# 05_-_POWER_REGULATION.net
KiCad netlist of a schematic drawn in Altium Designer
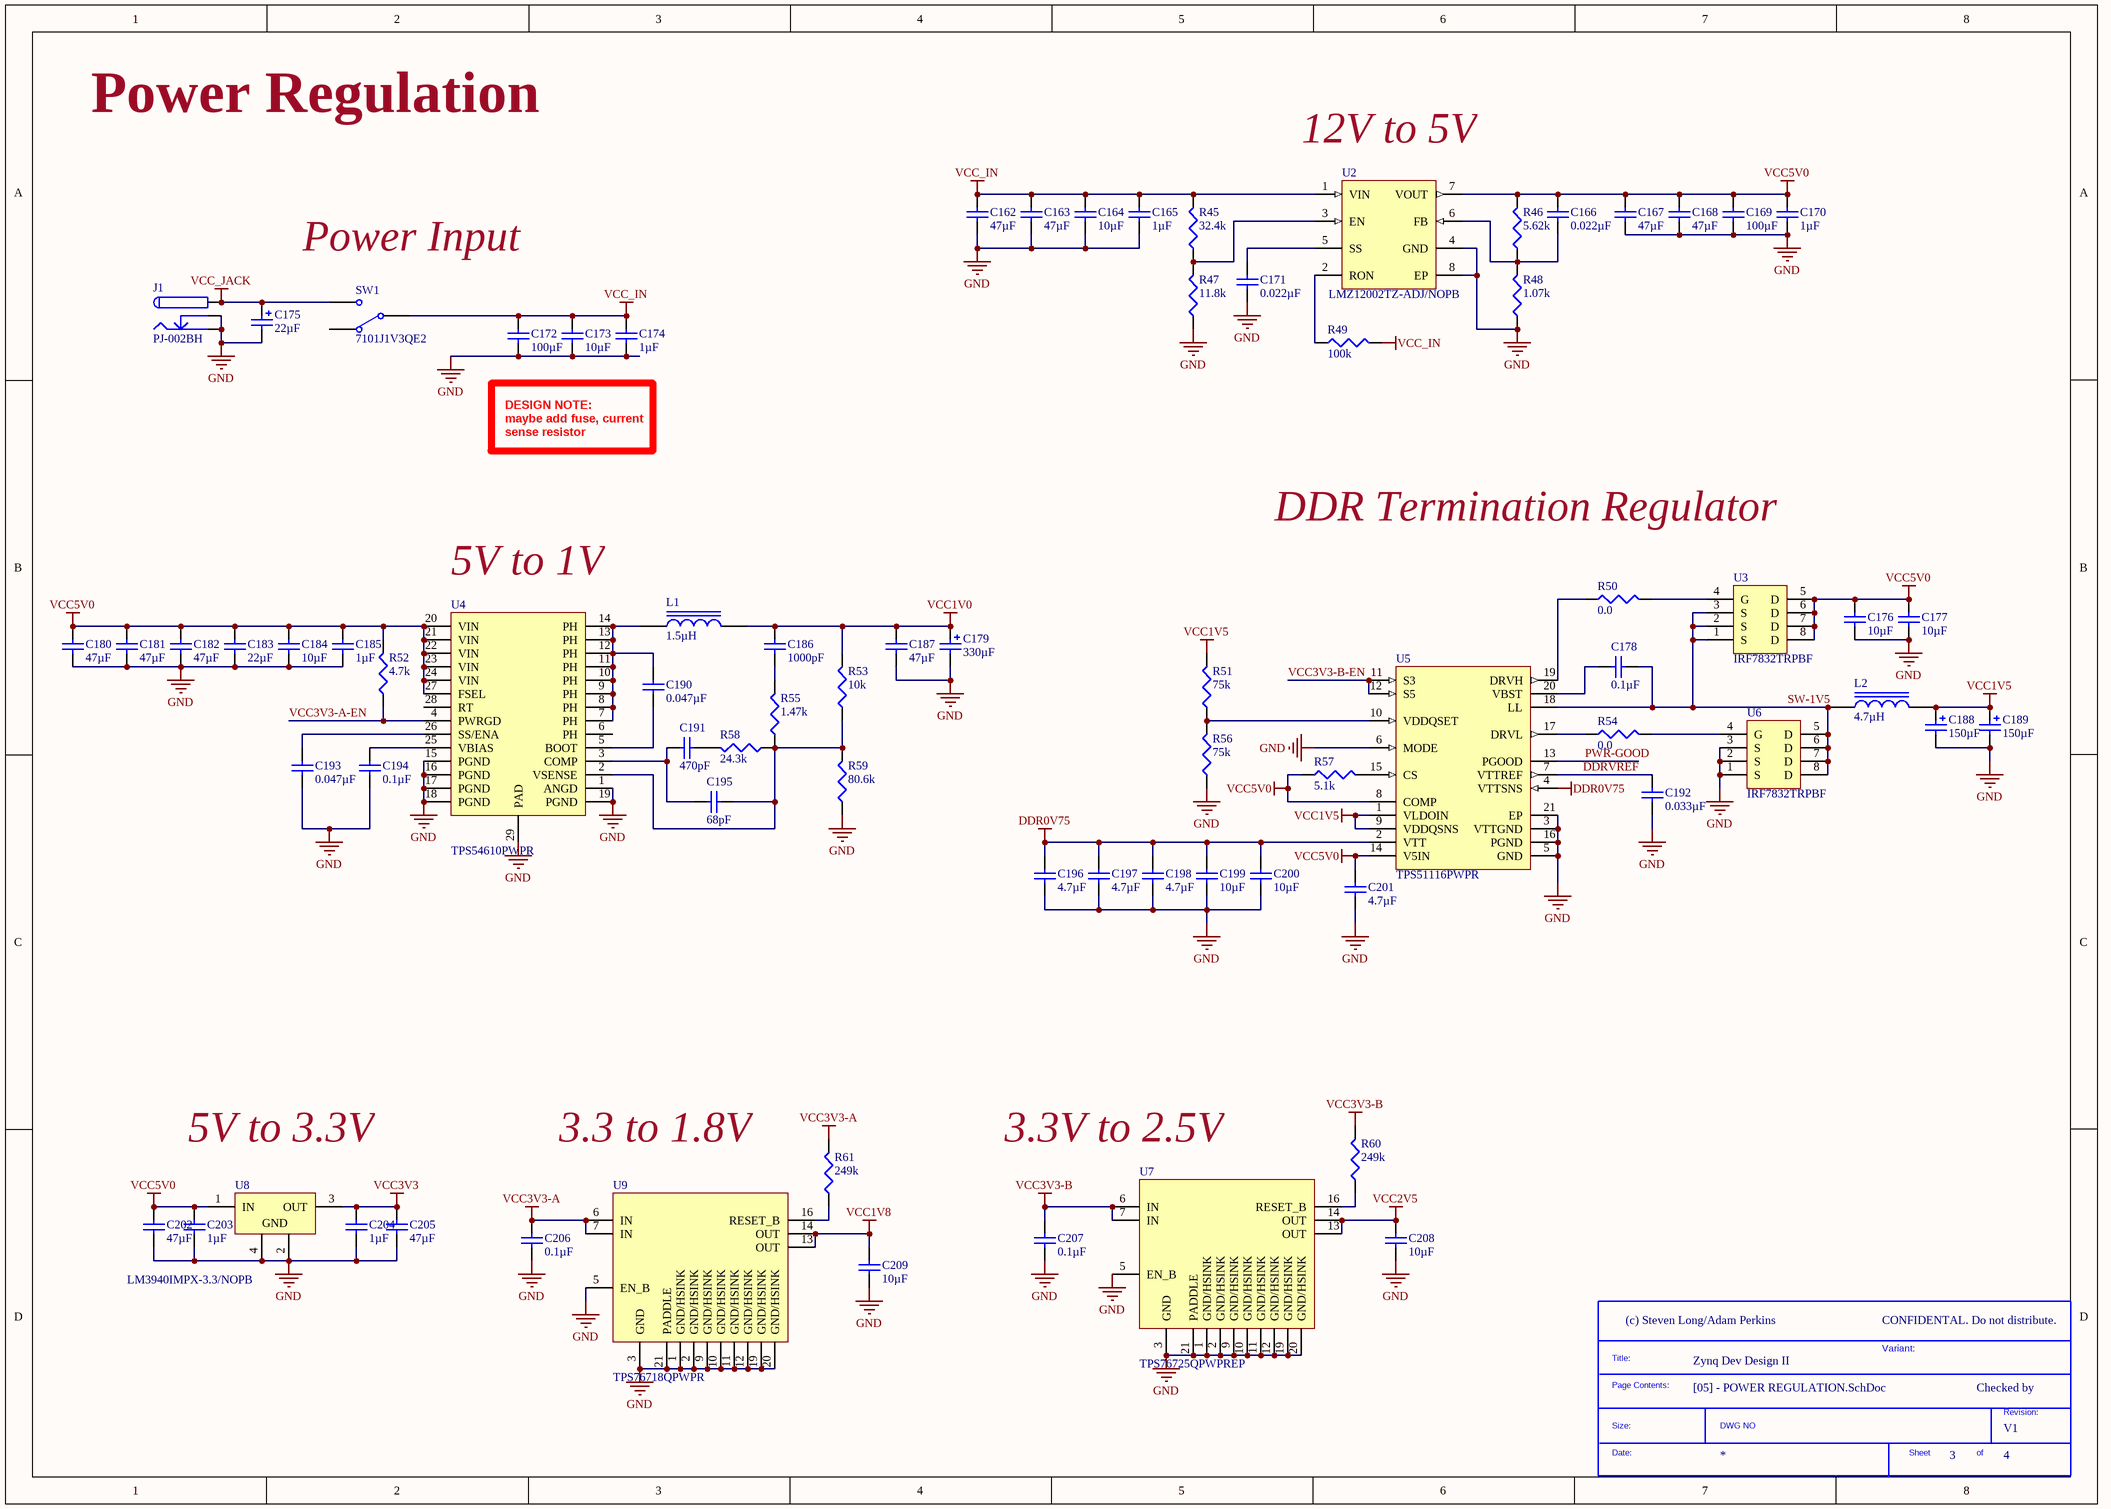
[diagram p0: [05] - POWER REGULATION.SchDoc]

(export (version "E")
  (design (tool "Eeschema 10.0.6"))
  (components
    (comp (ref "C162")
      (value "GRM32ER61C476ME15L")
      (footprint "CAP-1210")
      (description "CAP CER 47UF 16V X5R 1210")
      (fields
        (field (name "MANUFACTURER") "Murata Electronics North America")
        (field (name "TOLERANCE") "±20%")
        (field (name "CAPACITANCE") "47µF")
      )
      (libsource (lib "zynq_dev_V1") (part "GRM32ER61C476ME15L"))
    )
    (comp (ref "C163")
      (value "GRM32ER61C476ME15L")
      (footprint "CAP-1210")
      (description "CAP CER 47UF 16V X5R 1210")
      (fields
        (field (name "MANUFACTURER") "Murata Electronics North America")
        (field (name "TOLERANCE") "±20%")
        (field (name "CAPACITANCE") "47µF")
      )
      (libsource (lib "zynq_dev_V1") (part "GRM32ER61C476ME15L"))
    )
    (comp (ref "C164")
      (value "GRM21BR61E106KA73L")
      (footprint "CAP-0805")
      (description "CAP CER 10UF 25V X5R 0805")
      (fields
        (field (name "MANUFACTURER") "Murata Electronics North America")
        (field (name "TOLERANCE") "±10%")
        (field (name "CAPACITANCE") "10µF")
      )
      (libsource (lib "zynq_dev_V1") (part "GRM21BR61E106KA73L"))
    )
    (comp (ref "C165")
      (value "GRM188R71C105KA12D")
      (footprint "CAP-0603")
      (description "CAP CER 1UF 16V X7R 0603")
      (fields
        (field (name "MANUFACTURER") "Murata Electronics North America")
        (field (name "TOLERANCE") "±10%")
        (field (name "CAPACITANCE") "1µF")
      )
      (libsource (lib "zynq_dev_V1") (part "GRM188R71C105KA12D"))
    )
    (comp (ref "C166")
      (value "C1005X7R1E223K050BB")
      (footprint "CAP-0402")
      (description "CAP CER 0.022UF 25V X7R 0402")
      (fields
        (field (name "MANUFACTURER") "TDK Corporation")
        (field (name "TOLERANCE") "±10%")
        (field (name "CAPACITANCE") "0.022µF")
      )
      (libsource (lib "zynq_dev_V1") (part "C1005X7R1E223K050BB"))
    )
    (comp (ref "C167")
      (value "GRM32ER61C476ME15L")
      (footprint "CAP-1210")
      (description "CAP CER 47UF 16V X5R 1210")
      (fields
        (field (name "MANUFACTURER") "Murata Electronics North America")
        (field (name "TOLERANCE") "±20%")
        (field (name "CAPACITANCE") "47µF")
      )
      (libsource (lib "zynq_dev_V1") (part "GRM32ER61C476ME15L"))
    )
    (comp (ref "C168")
      (value "GRM32ER61C476ME15L")
      (footprint "CAP-1210")
      (description "CAP CER 47UF 16V X5R 1210")
      (fields
        (field (name "MANUFACTURER") "Murata Electronics North America")
        (field (name "TOLERANCE") "±20%")
        (field (name "CAPACITANCE") "47µF")
      )
      (libsource (lib "zynq_dev_V1") (part "GRM32ER61C476ME15L"))
    )
    (comp (ref "C169")
      (value "GRM32EE70G107ME19L")
      (footprint "CAP-1210")
      (description "CAP CER 100UF 4V X7U 1210")
      (fields
        (field (name "MANUFACTURER") "Murata Electronics North America")
        (field (name "TOLERANCE") "±20%")
        (field (name "CAPACITANCE") "100µF")
      )
      (libsource (lib "zynq_dev_V1") (part "GRM32EE70G107ME19L"))
    )
    (comp (ref "C170")
      (value "GRM188R71C105KA12D")
      (footprint "CAP-0603")
      (description "CAP CER 1UF 16V X7R 0603")
      (fields
        (field (name "MANUFACTURER") "Murata Electronics North America")
        (field (name "TOLERANCE") "±10%")
        (field (name "CAPACITANCE") "1µF")
      )
      (libsource (lib "zynq_dev_V1") (part "GRM188R71C105KA12D"))
    )
    (comp (ref "C171")
      (value "C1005X7R1E223K050BB")
      (footprint "CAP-0402")
      (description "CAP CER 0.022UF 25V X7R 0402")
      (fields
        (field (name "MANUFACTURER") "TDK Corporation")
        (field (name "TOLERANCE") "±10%")
        (field (name "CAPACITANCE") "0.022µF")
      )
      (libsource (lib "zynq_dev_V1") (part "C1005X7R1E223K050BB"))
    )
    (comp (ref "C172")
      (value "GRM32EE70G107ME19L")
      (footprint "CAP-1210")
      (description "CAP CER 100UF 4V X7U 1210")
      (fields
        (field (name "MANUFACTURER") "Murata Electronics North America")
        (field (name "TOLERANCE") "±20%")
        (field (name "CAPACITANCE") "100µF")
      )
      (libsource (lib "zynq_dev_V1") (part "GRM32EE70G107ME19L"))
    )
    (comp (ref "C173")
      (value "GRM21BR61E106KA73L")
      (footprint "CAP-0805")
      (description "CAP CER 10UF 25V X5R 0805")
      (fields
        (field (name "MANUFACTURER") "Murata Electronics North America")
        (field (name "TOLERANCE") "±10%")
        (field (name "CAPACITANCE") "10µF")
      )
      (libsource (lib "zynq_dev_V1") (part "GRM21BR61E106KA73L"))
    )
    (comp (ref "C174")
      (value "GRM188R71C105KA12D")
      (footprint "CAP-0603")
      (description "CAP CER 1UF 16V X7R 0603")
      (fields
        (field (name "MANUFACTURER") "Murata Electronics North America")
        (field (name "TOLERANCE") "±10%")
        (field (name "CAPACITANCE") "1µF")
      )
      (libsource (lib "zynq_dev_V1") (part "GRM188R71C105KA12D"))
    )
    (comp (ref "C175")
      (value "TAJB226K020RNJ")
      (footprint "CAP_POL_1210")
      (description "CAP TANT 22UF 20V 10% 1210")
      (fields
        (field (name "MANUFACTURER") "AVX Corporation")
        (field (name "TOLERANCE") "±10%")
        (field (name "CAPACITANCE") "22µF")
      )
      (libsource (lib "zynq_dev_V1") (part "TAJB226K020RNJ"))
    )
    (comp (ref "C176")
      (value "GRM21BR61E106KA73L")
      (footprint "CAP-0805")
      (description "CAP CER 10UF 25V X5R 0805")
      (fields
        (field (name "MANUFACTURER") "Murata Electronics North America")
        (field (name "TOLERANCE") "±10%")
        (field (name "CAPACITANCE") "10µF")
      )
      (libsource (lib "zynq_dev_V1") (part "GRM21BR61E106KA73L"))
    )
    (comp (ref "C177")
      (value "GRM21BR61E106KA73L")
      (footprint "CAP-0805")
      (description "CAP CER 10UF 25V X5R 0805")
      (fields
        (field (name "MANUFACTURER") "Murata Electronics North America")
        (field (name "TOLERANCE") "±10%")
        (field (name "CAPACITANCE") "10µF")
      )
      (libsource (lib "zynq_dev_V1") (part "GRM21BR61E106KA73L"))
    )
    (comp (ref "C178")
      (value "CGA2B1X7R1C104K050BC")
      (footprint "CAP-0402")
      (description "CAP CER 0.1UF 16V X7R 0402")
      (fields
        (field (name "MANUFACTURER") "TDK Corporation")
        (field (name "TOLERANCE") "±10%")
        (field (name "CAPACITANCE") "0.1µF")
      )
      (libsource (lib "zynq_dev_V1") (part "CGA2B1X7R1C104K050BC"))
    )
    (comp (ref "C179")
      (value "T530X337M010ATE004")
      (footprint "CAP_POL_2917")
      (description "CAP TANT POLY 330UF 10V 2917")
      (fields
        (field (name "MANUFACTURER") "Kemet")
        (field (name "TOLERANCE") "±20%")
        (field (name "CAPACITANCE") "330µF")
      )
      (libsource (lib "zynq_dev_V1") (part "T530X337M010ATE004"))
    )
    (comp (ref "C180")
      (value "GRM32ER61C476ME15L")
      (footprint "CAP-1210")
      (description "CAP CER 47UF 16V X5R 1210")
      (fields
        (field (name "MANUFACTURER") "Murata Electronics North America")
        (field (name "TOLERANCE") "±20%")
        (field (name "CAPACITANCE") "47µF")
      )
      (libsource (lib "zynq_dev_V1") (part "GRM32ER61C476ME15L"))
    )
    (comp (ref "C181")
      (value "GRM32ER61C476ME15L")
      (footprint "CAP-1210")
      (description "CAP CER 47UF 16V X5R 1210")
      (fields
        (field (name "MANUFACTURER") "Murata Electronics North America")
        (field (name "TOLERANCE") "±20%")
        (field (name "CAPACITANCE") "47µF")
      )
      (libsource (lib "zynq_dev_V1") (part "GRM32ER61C476ME15L"))
    )
    (comp (ref "C182")
      (value "GRM32ER61C476ME15L")
      (footprint "CAP-1210")
      (description "CAP CER 47UF 16V X5R 1210")
      (fields
        (field (name "MANUFACTURER") "Murata Electronics North America")
        (field (name "TOLERANCE") "±20%")
        (field (name "CAPACITANCE") "47µF")
      )
      (libsource (lib "zynq_dev_V1") (part "GRM32ER61C476ME15L"))
    )
    (comp (ref "C183")
      (value "GRM21BR61A226ME51L")
      (footprint "CAP-0805")
      (description "CAP CER 22UF 10V X5R 0805")
      (fields
        (field (name "MANUFACTURER") "Murata Electronics North America")
        (field (name "TOLERANCE") "±20%")
        (field (name "CAPACITANCE") "22µF")
      )
      (libsource (lib "zynq_dev_V1") (part "GRM21BR61A226ME51L"))
    )
    (comp (ref "C184")
      (value "GRM21BR61E106KA73L")
      (footprint "CAP-0805")
      (description "CAP CER 10UF 25V X5R 0805")
      (fields
        (field (name "MANUFACTURER") "Murata Electronics North America")
        (field (name "TOLERANCE") "±10%")
        (field (name "CAPACITANCE") "10µF")
      )
      (libsource (lib "zynq_dev_V1") (part "GRM21BR61E106KA73L"))
    )
    (comp (ref "C185")
      (value "GRM188R71C105KA12D")
      (footprint "CAP-0603")
      (description "CAP CER 1UF 16V X7R 0603")
      (fields
        (field (name "MANUFACTURER") "Murata Electronics North America")
        (field (name "TOLERANCE") "±10%")
        (field (name "CAPACITANCE") "1µF")
      )
      (libsource (lib "zynq_dev_V1") (part "GRM188R71C105KA12D"))
    )
    (comp (ref "C186")
      (value "CGA2B2X7R1H102K050BA")
      (footprint "CAP-0402")
      (description "CAP CER 1000PF 50V X7R 0402")
      (fields
        (field (name "MANUFACTURER") "TDK Corporation")
        (field (name "TOLERANCE") "±10%")
        (field (name "CAPACITANCE") "1000pF")
      )
      (libsource (lib "zynq_dev_V1") (part "CGA2B2X7R1H102K050BA"))
    )
    (comp (ref "C187")
      (value "GRM32ER61C476ME15L")
      (footprint "CAP-1210")
      (description "CAP CER 47UF 16V X5R 1210")
      (fields
        (field (name "MANUFACTURER") "Murata Electronics North America")
        (field (name "TOLERANCE") "±20%")
        (field (name "CAPACITANCE") "47µF")
      )
      (libsource (lib "zynq_dev_V1") (part "GRM32ER61C476ME15L"))
    )
    (comp (ref "C188")
      (value "TCJB157M006R0070")
      (description "CAP TANT POLY 150UF 6.3V 1210")
      (fields
        (field (name "MANUFACTURER") "AVX Corporation")
        (field (name "TOLERANCE") "±20%")
        (field (name "CAPACITANCE") "150µF")
      )
      (libsource (lib "zynq_dev_V1") (part "TCJB157M006R0070"))
    )
    (comp (ref "C189")
      (value "TCJB157M006R0070")
      (description "CAP TANT POLY 150UF 6.3V 1210")
      (fields
        (field (name "MANUFACTURER") "AVX Corporation")
        (field (name "TOLERANCE") "±20%")
        (field (name "CAPACITANCE") "150µF")
      )
      (libsource (lib "zynq_dev_V1") (part "TCJB157M006R0070"))
    )
    (comp (ref "C190")
      (value "CGA2B1X7R1E473K050BC")
      (footprint "CAP-0402")
      (description "CAP CER 0.047UF 25V X7R 0402")
      (fields
        (field (name "MANUFACTURER") "TDK Corporation")
        (field (name "TOLERANCE") "±10%")
        (field (name "CAPACITANCE") "0.047µF")
      )
      (libsource (lib "zynq_dev_V1") (part "CGA2B1X7R1E473K050BC"))
    )
    (comp (ref "C191")
      (value "CGA2B2X8R1H471K050BA")
      (footprint "CAP-0402")
      (description "CAP CER 470PF 50V X8R 0402")
      (fields
        (field (name "MANUFACTURER") "TDK Corporation")
        (field (name "TOLERANCE") "±10%")
        (field (name "CAPACITANCE") "470pF")
      )
      (libsource (lib "zynq_dev_V1") (part "CGA2B2X8R1H471K050BA"))
    )
    (comp (ref "C192")
      (value "CGA2B3X7R1H333K050BB")
      (footprint "CAP-0402")
      (description "CAP CER 0.033UF 50V X7R 0402")
      (fields
        (field (name "MANUFACTURER") "TDK Corporation")
        (field (name "TOLERANCE") "±10%")
        (field (name "CAPACITANCE") "0.033µF")
      )
      (libsource (lib "zynq_dev_V1") (part "CGA2B3X7R1H333K050BB"))
    )
    (comp (ref "C193")
      (value "CGA2B1X7R1E473K050BC")
      (footprint "CAP-0402")
      (description "CAP CER 0.047UF 25V X7R 0402")
      (fields
        (field (name "MANUFACTURER") "TDK Corporation")
        (field (name "TOLERANCE") "±10%")
        (field (name "CAPACITANCE") "0.047µF")
      )
      (libsource (lib "zynq_dev_V1") (part "CGA2B1X7R1E473K050BC"))
    )
    (comp (ref "C194")
      (value "CGA2B1X7R1C104K050BC")
      (footprint "CAP-0402")
      (description "CAP CER 0.1UF 16V X7R 0402")
      (fields
        (field (name "MANUFACTURER") "TDK Corporation")
        (field (name "TOLERANCE") "±10%")
        (field (name "CAPACITANCE") "0.1µF")
      )
      (libsource (lib "zynq_dev_V1") (part "CGA2B1X7R1C104K050BC"))
    )
    (comp (ref "C195")
      (value "CGA2B2C0G1H680J050BA")
      (footprint "CAP-0402")
      (description "CAP CER 68PF 50V C0G 0402")
      (fields
        (field (name "MANUFACTURER") "TDK Corporation")
        (field (name "TOLERANCE") "±5%")
        (field (name "CAPACITANCE") "68pF")
      )
      (libsource (lib "zynq_dev_V1") (part "CGA2B2C0G1H680J050BA"))
    )
    (comp (ref "C196")
      (value "GRM188R60J475KE19D")
      (footprint "CAP-0603")
      (description "CAP CER 4.7UF 6.3V X5R 0603")
      (fields
        (field (name "MANUFACTURER") "Murata Electronics North America")
        (field (name "TOLERANCE") "±10%")
        (field (name "CAPACITANCE") "4.7µF")
      )
      (libsource (lib "zynq_dev_V1") (part "GRM188R60J475KE19D"))
    )
    (comp (ref "C197")
      (value "GRM188R60J475KE19D")
      (footprint "CAP-0603")
      (description "CAP CER 4.7UF 6.3V X5R 0603")
      (fields
        (field (name "MANUFACTURER") "Murata Electronics North America")
        (field (name "TOLERANCE") "±10%")
        (field (name "CAPACITANCE") "4.7µF")
      )
      (libsource (lib "zynq_dev_V1") (part "GRM188R60J475KE19D"))
    )
    (comp (ref "C198")
      (value "GRM188R60J475KE19D")
      (footprint "CAP-0603")
      (description "CAP CER 4.7UF 6.3V X5R 0603")
      (fields
        (field (name "MANUFACTURER") "Murata Electronics North America")
        (field (name "TOLERANCE") "±10%")
        (field (name "CAPACITANCE") "4.7µF")
      )
      (libsource (lib "zynq_dev_V1") (part "GRM188R60J475KE19D"))
    )
    (comp (ref "C199")
      (value "GRM21BR61E106KA73L")
      (footprint "CAP-0805")
      (description "CAP CER 10UF 25V X5R 0805")
      (fields
        (field (name "MANUFACTURER") "Murata Electronics North America")
        (field (name "TOLERANCE") "±10%")
        (field (name "CAPACITANCE") "10µF")
      )
      (libsource (lib "zynq_dev_V1") (part "GRM21BR61E106KA73L"))
    )
    (comp (ref "C200")
      (value "GRM21BR61E106KA73L")
      (footprint "CAP-0805")
      (description "CAP CER 10UF 25V X5R 0805")
      (fields
        (field (name "MANUFACTURER") "Murata Electronics North America")
        (field (name "TOLERANCE") "±10%")
        (field (name "CAPACITANCE") "10µF")
      )
      (libsource (lib "zynq_dev_V1") (part "GRM21BR61E106KA73L"))
    )
    (comp (ref "C201")
      (value "CGA4J3X7R1C475K125AB")
      (footprint "CAP-0805")
      (description "CAP CER 4.7UF 16V X7R 0805")
      (fields
        (field (name "MANUFACTURER") "TDK Corporation")
        (field (name "TOLERANCE") "±10%")
        (field (name "CAPACITANCE") "4.7µF")
      )
      (libsource (lib "zynq_dev_V1") (part "CGA4J3X7R1C475K125AB"))
    )
    (comp (ref "C202")
      (value "GRM32ER61C476ME15L")
      (footprint "CAP-1210")
      (description "CAP CER 47UF 16V X5R 1210")
      (fields
        (field (name "MANUFACTURER") "Murata Electronics North America")
        (field (name "TOLERANCE") "±20%")
        (field (name "CAPACITANCE") "47µF")
      )
      (libsource (lib "zynq_dev_V1") (part "GRM32ER61C476ME15L"))
    )
    (comp (ref "C203")
      (value "GRM188R71C105KA12D")
      (footprint "CAP-0603")
      (description "CAP CER 1UF 16V X7R 0603")
      (fields
        (field (name "MANUFACTURER") "Murata Electronics North America")
        (field (name "TOLERANCE") "±10%")
        (field (name "CAPACITANCE") "1µF")
      )
      (libsource (lib "zynq_dev_V1") (part "GRM188R71C105KA12D"))
    )
    (comp (ref "C204")
      (value "GRM188R71C105KA12D")
      (footprint "CAP-0603")
      (description "CAP CER 1UF 16V X7R 0603")
      (fields
        (field (name "MANUFACTURER") "Murata Electronics North America")
        (field (name "TOLERANCE") "±10%")
        (field (name "CAPACITANCE") "1µF")
      )
      (libsource (lib "zynq_dev_V1") (part "GRM188R71C105KA12D"))
    )
    (comp (ref "C205")
      (value "GRM32ER61C476ME15L")
      (footprint "CAP-1210")
      (description "CAP CER 47UF 16V X5R 1210")
      (fields
        (field (name "MANUFACTURER") "Murata Electronics North America")
        (field (name "TOLERANCE") "±20%")
        (field (name "CAPACITANCE") "47µF")
      )
      (libsource (lib "zynq_dev_V1") (part "GRM32ER61C476ME15L"))
    )
    (comp (ref "C206")
      (value "CGA2B1X7R1C104K050BC")
      (footprint "CAP-0402")
      (description "CAP CER 0.1UF 16V X7R 0402")
      (fields
        (field (name "MANUFACTURER") "TDK Corporation")
        (field (name "TOLERANCE") "±10%")
        (field (name "CAPACITANCE") "0.1µF")
      )
      (libsource (lib "zynq_dev_V1") (part "CGA2B1X7R1C104K050BC"))
    )
    (comp (ref "C207")
      (value "CGA2B1X7R1C104K050BC")
      (footprint "CAP-0402")
      (description "CAP CER 0.1UF 16V X7R 0402")
      (fields
        (field (name "MANUFACTURER") "TDK Corporation")
        (field (name "TOLERANCE") "±10%")
        (field (name "CAPACITANCE") "0.1µF")
      )
      (libsource (lib "zynq_dev_V1") (part "CGA2B1X7R1C104K050BC"))
    )
    (comp (ref "C208")
      (value "GRM21BR61E106KA73L")
      (footprint "CAP-0805")
      (description "CAP CER 10UF 25V X5R 0805")
      (fields
        (field (name "MANUFACTURER") "Murata Electronics North America")
        (field (name "TOLERANCE") "±10%")
        (field (name "CAPACITANCE") "10µF")
      )
      (libsource (lib "zynq_dev_V1") (part "GRM21BR61E106KA73L"))
    )
    (comp (ref "C209")
      (value "GRM21BR61E106KA73L")
      (footprint "CAP-0805")
      (description "CAP CER 10UF 25V X5R 0805")
      (fields
        (field (name "MANUFACTURER") "Murata Electronics North America")
        (field (name "TOLERANCE") "±10%")
        (field (name "CAPACITANCE") "10µF")
      )
      (libsource (lib "zynq_dev_V1") (part "GRM21BR61E106KA73L"))
    )
    (comp (ref "J1")
      (value "PJ-002BH")
      (footprint "PJ-002BH")
      (description "CONN PWR JACK 2.5X5.5MM HIGH CUR")
      (fields (field (name "MANUFACTURER") "CUI Inc."))
      (libsource (lib "zynq_dev_V1") (part "PJ-002BH"))
    )
    (comp (ref "L1")
      (value "SRU1048-1R5Y")
      (footprint "INDP9898X51N")
      (description "FIXED IND 1.5UH 7A 4.3 MOHM SMD")
      (fields
        (field (name "MANUFACTURER") "Bourns Inc.")
        (field (name "TOLERANCE") "±30%")
        (field (name "INDUCTANCE") "1.5µH")
      )
      (libsource (lib "zynq_dev_V1") (part "SRU1048-1R5Y"))
    )
    (comp (ref "L2")
      (value "SRU1048-4R7Y")
      (footprint "INDP9898X51N")
      (description "FIXED IND 4.7UH 5.5A 9.5 MOHM")
      (fields
        (field (name "MANUFACTURER") "Bourns Inc.")
        (field (name "TOLERANCE") "±30%")
        (field (name "INDUCTANCE") "4.7µH")
      )
      (libsource (lib "zynq_dev_V1") (part "SRU1048-4R7Y"))
    )
    (comp (ref "R45")
      (value "ERJ-2RKF3242X")
      (footprint "R0402")
      (description "RES SMD 32.4K OHM 1% 1/10W 0402")
      (fields
        (field (name "MANUFACTURER") "Panasonic Electronic Components")
        (field (name "TOLERANCE") "±1%")
        (field (name "RESISTANCE (OHMS)") "32.4k")
      )
      (libsource (lib "zynq_dev_V1") (part "ERJ-2RKF3242X"))
    )
    (comp (ref "R46")
      (value "ERJ-2RKF5621X")
      (footprint "R0402")
      (description "RES SMD 5.62K OHM 1% 1/10W 0402")
      (fields
        (field (name "MANUFACTURER") "Panasonic Electronic Components")
        (field (name "TOLERANCE") "±1%")
        (field (name "RESISTANCE (OHMS)") "5.62k")
      )
      (libsource (lib "zynq_dev_V1") (part "ERJ-2RKF5621X"))
    )
    (comp (ref "R47")
      (value "ERJ-2RKF1182X")
      (footprint "R0402")
      (description "RES SMD 11.8K OHM 1% 1/10W 0402")
      (fields
        (field (name "MANUFACTURER") "Panasonic Electronic Components")
        (field (name "TOLERANCE") "±1%")
        (field (name "RESISTANCE (OHMS)") "11.8k")
      )
      (libsource (lib "zynq_dev_V1") (part "ERJ-2RKF1182X"))
    )
    (comp (ref "R48")
      (value "ERJ-2RKF1071X")
      (footprint "R0402")
      (description "RES SMD 1.07K OHM 1% 1/10W 0402")
      (fields
        (field (name "MANUFACTURER") "Panasonic Electronic Components")
        (field (name "TOLERANCE") "±1%")
        (field (name "RESISTANCE (OHMS)") "1.07k")
      )
      (libsource (lib "zynq_dev_V1") (part "ERJ-2RKF1071X"))
    )
    (comp (ref "R49")
      (value "ERJ-2RKF1003X")
      (footprint "R0402")
      (description "RES SMD 100K OHM 1% 1/10W 0402")
      (fields
        (field (name "MANUFACTURER") "Panasonic Electronic Components")
        (field (name "TOLERANCE") "±1%")
        (field (name "RESISTANCE (OHMS)") "100k")
      )
      (libsource (lib "zynq_dev_V1") (part "ERJ-2RKF1003X"))
    )
    (comp (ref "R50")
      (value "ERJ-2GE0R00X")
      (footprint "R0402")
      (description "RES SMD 0.0OHM JUMPER 1/10W 0402")
      (fields
        (field (name "MANUFACTURER") "Panasonic Electronic Components")
        (field (name "TOLERANCE") "Jumper")
        (field (name "RESISTANCE (OHMS)") "0.0")
      )
      (libsource (lib "zynq_dev_V1") (part "ERJ-2GE0R00X"))
    )
    (comp (ref "R51")
      (value "ERJ-2RKF7502X")
      (footprint "R0402")
      (description "RES SMD 75K OHM 1% 1/10W 0402")
      (fields
        (field (name "MANUFACTURER") "Panasonic Electronic Components")
        (field (name "TOLERANCE") "±1%")
        (field (name "RESISTANCE (OHMS)") "75k")
      )
      (libsource (lib "zynq_dev_V1") (part "ERJ-2RKF7502X"))
    )
    (comp (ref "R52")
      (value "ERJ-3EKF4701V")
      (footprint "R0603")
      (description "RES SMD 4.7K OHM 1% 1/10W 0603")
      (fields
        (field (name "MANUFACTURER") "Panasonic Electronic Components")
        (field (name "TOLERANCE") "±1%")
        (field (name "RESISTANCE (OHMS)") "4.7k")
      )
      (libsource (lib "zynq_dev_V1") (part "ERJ-3EKF4701V"))
    )
    (comp (ref "R53")
      (value "RC0402FR-0710KL")
      (footprint "R0402")
      (description "RES SMD 10K OHM 1% 1/16W 0402")
      (fields
        (field (name "MANUFACTURER") "Yageo")
        (field (name "TOLERANCE") "±1%")
        (field (name "RESISTANCE (OHMS)") "10k")
      )
      (libsource (lib "zynq_dev_V1") (part "RC0402FR-0710KL"))
    )
    (comp (ref "R54")
      (value "ERJ-2GE0R00X")
      (footprint "R0402")
      (description "RES SMD 0.0OHM JUMPER 1/10W 0402")
      (fields
        (field (name "MANUFACTURER") "Panasonic Electronic Components")
        (field (name "TOLERANCE") "Jumper")
        (field (name "RESISTANCE (OHMS)") "0.0")
      )
      (libsource (lib "zynq_dev_V1") (part "ERJ-2GE0R00X"))
    )
    (comp (ref "R55")
      (value "ERA-2AEB1471X")
      (footprint "R0402")
      (description "RES SMD 1.47KOHM 0.1% 1/16W 0402")
      (fields
        (field (name "MANUFACTURER") "Panasonic Electronic Components")
        (field (name "TOLERANCE") "±0.1%")
        (field (name "RESISTANCE (OHMS)") "1.47k")
      )
      (libsource (lib "zynq_dev_V1") (part "ERA-2AEB1471X"))
    )
    (comp (ref "R56")
      (value "ERJ-2RKF7502X")
      (footprint "R0402")
      (description "RES SMD 75K OHM 1% 1/10W 0402")
      (fields
        (field (name "MANUFACTURER") "Panasonic Electronic Components")
        (field (name "TOLERANCE") "±1%")
        (field (name "RESISTANCE (OHMS)") "75k")
      )
      (libsource (lib "zynq_dev_V1") (part "ERJ-2RKF7502X"))
    )
    (comp (ref "R57")
      (value "CRCW04025K10FKED")
      (footprint "R0402")
      (description "RES SMD 5.1K OHM 1% 1/16W 0402")
      (fields
        (field (name "MANUFACTURER") "Vishay Dale")
        (field (name "TOLERANCE") "±1%")
        (field (name "RESISTANCE (OHMS)") "5.1k")
      )
      (libsource (lib "zynq_dev_V1") (part "CRCW04025K10FKED"))
    )
    (comp (ref "R58")
      (value "ERJ-2RKF2432X")
      (footprint "R0402")
      (description "RES SMD 24.3K OHM 1% 1/10W 0402")
      (fields
        (field (name "MANUFACTURER") "Panasonic Electronic Components")
        (field (name "TOLERANCE") "±1%")
        (field (name "RESISTANCE (OHMS)") "24.3k")
      )
      (libsource (lib "zynq_dev_V1") (part "ERJ-2RKF2432X"))
    )
    (comp (ref "R59")
      (value "ERA-2AEB8062X")
      (footprint "R0402")
      (description "RES SMD 80.6KOHM 0.1% 1/16W 0402")
      (fields
        (field (name "MANUFACTURER") "Panasonic Electronic Components")
        (field (name "TOLERANCE") "±0.1%")
        (field (name "RESISTANCE (OHMS)") "80.6k")
      )
      (libsource (lib "zynq_dev_V1") (part "ERA-2AEB8062X"))
    )
    (comp (ref "R60")
      (value "ERJ-2RKF2493X")
      (footprint "R0402")
      (description "RES SMD 249K OHM 1% 1/10W 0402")
      (fields
        (field (name "MANUFACTURER") "Panasonic Electronic Components")
        (field (name "TOLERANCE") "±1%")
        (field (name "RESISTANCE (OHMS)") "249k")
      )
      (libsource (lib "zynq_dev_V1") (part "ERJ-2RKF2493X"))
    )
    (comp (ref "R61")
      (value "ERJ-2RKF2493X")
      (footprint "R0402")
      (description "RES SMD 249K OHM 1% 1/10W 0402")
      (fields
        (field (name "MANUFACTURER") "Panasonic Electronic Components")
        (field (name "TOLERANCE") "±1%")
        (field (name "RESISTANCE (OHMS)") "249k")
      )
      (libsource (lib "zynq_dev_V1") (part "ERJ-2RKF2493X"))
    )
    (comp (ref "SW1")
      (value "7101J1V3QE2")
      (footprint "SPDT")
      (description "SWITCH ROCKER SPDT 5A 120V")
      (fields (field (name "MANUFACTURER") "C&K Components"))
      (libsource (lib "zynq_dev_V1") (part "7101J1V3QE2"))
    )
    (comp (ref "U2")
      (value "LMZ12002TZ-ADJ/NOPB")
      (footprint "TZA07A_V")
      (description "IC BUCK SYNC ADJ 2A TO-PMOD-7")
      (fields (field (name "MANUFACTURER") "Texas Instruments"))
      (libsource (lib "zynq_dev_V1") (part "LMZ12002TZ-ADJ/NOPB"))
    )
    (comp (ref "U3")
      (value "IRF7832TRPBF")
      (footprint "SOIC127P600X175-8N")
      (description "MOSFET N-CH 30V 20A 8-SOIC")
      (fields (field (name "MANUFACTURER") "Infineon Technologies Americas Corp."))
      (libsource (lib "zynq_dev_V1") (part "IRF7832TRPBF"))
    )
    (comp (ref "U4")
      (value "TPS54610PWPR")
      (footprint "TSOP65P640X120_HS-29N")
      (description "IC REG BUCK ADJ 6A SYNC 28HTSSOP")
      (fields (field (name "MANUFACTURER") "Texas Instruments"))
      (libsource (lib "zynq_dev_V1") (part "TPS54610PWPR"))
    )
    (comp (ref "U5")
      (value "TPS51116PWPR")
      (footprint "TSOP65P640X120_HS-21N")
      (description "IC DDR SYNC BUC CTRL REF20HTSSOP")
      (fields (field (name "MANUFACTURER") "Texas Instruments"))
      (libsource (lib "zynq_dev_V1") (part "TPS51116PWPR"))
    )
    (comp (ref "U6")
      (value "IRF7832TRPBF")
      (footprint "SOIC127P600X175-8N")
      (description "MOSFET N-CH 30V 20A 8-SOIC")
      (fields (field (name "MANUFACTURER") "Infineon Technologies Americas Corp."))
      (libsource (lib "zynq_dev_V1") (part "IRF7832TRPBF"))
    )
    (comp (ref "U7")
      (value "TPS76725QPWPREP")
      (footprint "TSOP65P640X120_HS-21N")
      (description "IC REG LDO 2.5V 1A 20HTSSOP")
      (fields (field (name "MANUFACTURER") "Texas Instruments"))
      (libsource (lib "zynq_dev_V1") (part "TPS76725QPWPREP"))
    )
    (comp (ref "U8")
      (value "LM3940IMPX-3.3/NOPB")
      (footprint "SOT230P700X180-4N")
      (description "IC REG LDO 3.3V 1A SOT223")
      (fields (field (name "MANUFACTURER") "Texas Instruments"))
      (libsource (lib "zynq_dev_V1") (part "LM3940IMPX-3.3/NOPB"))
    )
    (comp (ref "U9")
      (value "TPS76718QPWPR")
      (footprint "TSOP65P640X120_HS-21N")
      (description "IC REG LDO 1.8V 1A 20HTSSOP")
      (fields (field (name "MANUFACTURER") "Texas Instruments"))
      (libsource (lib "zynq_dev_V1") (part "TPS76718QPWPR"))
    )
  )
  (nets
    (net (code "1") (name "/DDRVREF") (class "Default")
      (node (ref "C192") (pin "1") (pinfunction "1_1") (pintype "passive"))
      (node (ref "U5") (pin "7") (pinfunction "VTTREF_7") (pintype "output"))
    )
    (net (code "2") (name "/PWR-GOOD") (class "Default")
      (node (ref "U5") (pin "13") (pinfunction "PGOOD_13") (pintype "open_collector"))
    )
    (net (code "3") (name "/SW-1V5") (class "Default")
      (node (ref "C178") (pin "1") (pinfunction "1_1") (pintype "passive"))
      (node (ref "L2") (pin "1") (pinfunction "1_1") (pintype "passive"))
      (node (ref "U3") (pin "1") (pinfunction "S_1") (pintype "passive"))
      (node (ref "U3") (pin "2") (pinfunction "S_2") (pintype "passive"))
      (node (ref "U3") (pin "3") (pinfunction "S_3") (pintype "passive"))
      (node (ref "U5") (pin "18") (pinfunction "LL_18") (pintype "power_in"))
      (node (ref "U6") (pin "5") (pinfunction "D_5") (pintype "passive"))
      (node (ref "U6") (pin "6") (pinfunction "D_6") (pintype "passive"))
      (node (ref "U6") (pin "7") (pinfunction "D_7") (pintype "passive"))
      (node (ref "U6") (pin "8") (pinfunction "D_8") (pintype "passive"))
    )
    (net (code "4") (name "/VCC3V3-A-EN") (class "Default")
      (node (ref "R52") (pin "1") (pinfunction "1_1") (pintype "passive"))
      (node (ref "U4") (pin "4") (pinfunction "PWRGD_4") (pintype "passive"))
    )
    (net (code "5") (name "/VCC3V3-B-EN") (class "Default")
      (node (ref "U5") (pin "11") (pinfunction "S3_11") (pintype "input"))
      (node (ref "U5") (pin "12") (pinfunction "S5_12") (pintype "input"))
    )
    (net (code "6") (name "DDR0V75") (class "Default")
      (node (ref "C196") (pin "1") (pinfunction "1_1") (pintype "passive"))
      (node (ref "C197") (pin "1") (pinfunction "1_1") (pintype "passive"))
      (node (ref "C198") (pin "1") (pinfunction "1_1") (pintype "passive"))
      (node (ref "C199") (pin "1") (pinfunction "1_1") (pintype "passive"))
      (node (ref "C200") (pin "1") (pinfunction "1_1") (pintype "passive"))
      (node (ref "U5") (pin "2") (pinfunction "VTT_2") (pintype "power_in"))
      (node (ref "U5") (pin "4") (pinfunction "VTTSNS_4") (pintype "input"))
    )
    (net (code "7") (name "GND") (class "Default")
      (node (ref "C162") (pin "2") (pinfunction "2_2") (pintype "passive"))
      (node (ref "C163") (pin "2") (pinfunction "2_2") (pintype "passive"))
      (node (ref "C164") (pin "2") (pinfunction "2_2") (pintype "passive"))
      (node (ref "C165") (pin "2") (pinfunction "2_2") (pintype "passive"))
      (node (ref "C167") (pin "2") (pinfunction "2_2") (pintype "passive"))
      (node (ref "C168") (pin "2") (pinfunction "2_2") (pintype "passive"))
      (node (ref "C169") (pin "2") (pinfunction "2_2") (pintype "passive"))
      (node (ref "C170") (pin "2") (pinfunction "2_2") (pintype "passive"))
      (node (ref "C171") (pin "2") (pinfunction "2_2") (pintype "passive"))
      (node (ref "C172") (pin "2") (pinfunction "2_2") (pintype "passive"))
      (node (ref "C173") (pin "2") (pinfunction "2_2") (pintype "passive"))
      (node (ref "C174") (pin "2") (pinfunction "2_2") (pintype "passive"))
      (node (ref "C175") (pin "2") (pinfunction "2_2") (pintype "passive"))
      (node (ref "C176") (pin "2") (pinfunction "2_2") (pintype "passive"))
      (node (ref "C177") (pin "2") (pinfunction "2_2") (pintype "passive"))
      (node (ref "C179") (pin "1") (pinfunction "1_1") (pintype "passive"))
      (node (ref "C180") (pin "2") (pinfunction "2_2") (pintype "passive"))
      (node (ref "C181") (pin "2") (pinfunction "2_2") (pintype "passive"))
      (node (ref "C182") (pin "2") (pinfunction "2_2") (pintype "passive"))
      (node (ref "C183") (pin "2") (pinfunction "2_2") (pintype "passive"))
      (node (ref "C184") (pin "2") (pinfunction "2_2") (pintype "passive"))
      (node (ref "C185") (pin "2") (pinfunction "2_2") (pintype "passive"))
      (node (ref "C187") (pin "2") (pinfunction "2_2") (pintype "passive"))
      (node (ref "C188") (pin "2") (pinfunction "2_2") (pintype "passive"))
      (node (ref "C189") (pin "2") (pinfunction "2_2") (pintype "passive"))
      (node (ref "C192") (pin "2") (pinfunction "2_2") (pintype "passive"))
      (node (ref "C193") (pin "2") (pinfunction "2_2") (pintype "passive"))
      (node (ref "C194") (pin "2") (pinfunction "2_2") (pintype "passive"))
      (node (ref "C196") (pin "2") (pinfunction "2_2") (pintype "passive"))
      (node (ref "C197") (pin "2") (pinfunction "2_2") (pintype "passive"))
      (node (ref "C198") (pin "2") (pinfunction "2_2") (pintype "passive"))
      (node (ref "C199") (pin "2") (pinfunction "2_2") (pintype "passive"))
      (node (ref "C200") (pin "2") (pinfunction "2_2") (pintype "passive"))
      (node (ref "C201") (pin "2") (pinfunction "2_2") (pintype "passive"))
      (node (ref "C202") (pin "1") (pinfunction "1_1") (pintype "passive"))
      (node (ref "C203") (pin "1") (pinfunction "1_1") (pintype "passive"))
      (node (ref "C204") (pin "1") (pinfunction "1_1") (pintype "passive"))
      (node (ref "C205") (pin "1") (pinfunction "1_1") (pintype "passive"))
      (node (ref "C206") (pin "2") (pinfunction "2_2") (pintype "passive"))
      (node (ref "C207") (pin "2") (pinfunction "2_2") (pintype "passive"))
      (node (ref "C208") (pin "2") (pinfunction "2_2") (pintype "passive"))
      (node (ref "C209") (pin "2") (pinfunction "2_2") (pintype "passive"))
      (node (ref "J1") (pin "2") (pinfunction "2_2") (pintype "power_in"))
      (node (ref "J1") (pin "3") (pinfunction "3_3") (pintype "power_in"))
      (node (ref "R47") (pin "1") (pinfunction "1_1") (pintype "passive"))
      (node (ref "R48") (pin "1") (pinfunction "1_1") (pintype "passive"))
      (node (ref "R56") (pin "1") (pinfunction "1_1") (pintype "passive"))
      (node (ref "R59") (pin "1") (pinfunction "1_1") (pintype "passive"))
      (node (ref "U2") (pin "4") (pinfunction "GND_4") (pintype "power_in"))
      (node (ref "U2") (pin "8") (pinfunction "EP_8") (pintype "passive"))
      (node (ref "U4") (pin "1") (pinfunction "ANGD_1") (pintype "passive"))
      (node (ref "U4") (pin "15") (pinfunction "PGND_15") (pintype "passive"))
      (node (ref "U4") (pin "16") (pinfunction "PGND_16") (pintype "passive"))
      (node (ref "U4") (pin "17") (pinfunction "PGND_17") (pintype "passive"))
      (node (ref "U4") (pin "18") (pinfunction "PGND_18") (pintype "passive"))
      (node (ref "U4") (pin "19") (pinfunction "PGND_19") (pintype "passive"))
      (node (ref "U4") (pin "29") (pinfunction "PAD_29") (pintype "passive"))
      (node (ref "U5") (pin "16") (pinfunction "PGND_16") (pintype "power_in"))
      (node (ref "U5") (pin "21") (pinfunction "EP_21") (pintype "power_in"))
      (node (ref "U5") (pin "3") (pinfunction "VTTGND_3") (pintype "power_in"))
      (node (ref "U5") (pin "5") (pinfunction "GND_5") (pintype "power_in"))
      (node (ref "U5") (pin "6") (pinfunction "MODE_6") (pintype "input"))
      (node (ref "U6") (pin "1") (pinfunction "S_1") (pintype "passive"))
      (node (ref "U6") (pin "2") (pinfunction "S_2") (pintype "passive"))
      (node (ref "U6") (pin "3") (pinfunction "S_3") (pintype "passive"))
      (node (ref "U7") (pin "1") (pinfunction "GND/HSINK_1") (pintype "passive"))
      (node (ref "U7") (pin "10") (pinfunction "GND/HSINK_10") (pintype "passive"))
      (node (ref "U7") (pin "11") (pinfunction "GND/HSINK_11") (pintype "passive"))
      (node (ref "U7") (pin "12") (pinfunction "GND/HSINK_12") (pintype "passive"))
      (node (ref "U7") (pin "19") (pinfunction "GND/HSINK_19") (pintype "passive"))
      (node (ref "U7") (pin "2") (pinfunction "GND/HSINK_2") (pintype "passive"))
      (node (ref "U7") (pin "20") (pinfunction "GND/HSINK_20") (pintype "passive"))
      (node (ref "U7") (pin "21") (pinfunction "PADDLE_21") (pintype "passive"))
      (node (ref "U7") (pin "3") (pinfunction "GND_3") (pintype "passive"))
      (node (ref "U7") (pin "5") (pinfunction "EN_B_5") (pintype "passive"))
      (node (ref "U7") (pin "9") (pinfunction "GND/HSINK_9") (pintype "passive"))
      (node (ref "U8") (pin "2") (pinfunction "GND_2") (pintype "power_in"))
      (node (ref "U8") (pin "4") (pinfunction "GND_4") (pintype "power_in"))
      (node (ref "U9") (pin "1") (pinfunction "GND/HSINK_1") (pintype "passive"))
      (node (ref "U9") (pin "10") (pinfunction "GND/HSINK_10") (pintype "passive"))
      (node (ref "U9") (pin "11") (pinfunction "GND/HSINK_11") (pintype "passive"))
      (node (ref "U9") (pin "12") (pinfunction "GND/HSINK_12") (pintype "passive"))
      (node (ref "U9") (pin "19") (pinfunction "GND/HSINK_19") (pintype "passive"))
      (node (ref "U9") (pin "2") (pinfunction "GND/HSINK_2") (pintype "passive"))
      (node (ref "U9") (pin "20") (pinfunction "GND/HSINK_20") (pintype "passive"))
      (node (ref "U9") (pin "21") (pinfunction "PADDLE_21") (pintype "passive"))
      (node (ref "U9") (pin "3") (pinfunction "GND_3") (pintype "passive"))
      (node (ref "U9") (pin "5") (pinfunction "EN_B_5") (pintype "passive"))
      (node (ref "U9") (pin "9") (pinfunction "GND/HSINK_9") (pintype "passive"))
    )
    (net (code "8") (name "Net-(C186-Pad2)") (class "Default")
      (node (ref "C186") (pin "2") (pinfunction "2_2") (pintype "passive"))
      (node (ref "R55") (pin "2") (pinfunction "2_2") (pintype "passive"))
    )
    (net (code "9") (name "Net-(C190-Pad1)") (class "Default")
      (node (ref "C190") (pin "1") (pinfunction "1_1") (pintype "passive"))
      (node (ref "L1") (pin "1") (pinfunction "1_1") (pintype "passive"))
      (node (ref "U4") (pin "10") (pinfunction "PH_10") (pintype "passive"))
      (node (ref "U4") (pin "11") (pinfunction "PH_11") (pintype "passive"))
      (node (ref "U4") (pin "12") (pinfunction "PH_12") (pintype "passive"))
      (node (ref "U4") (pin "13") (pinfunction "PH_13") (pintype "passive"))
      (node (ref "U4") (pin "14") (pinfunction "PH_14") (pintype "passive"))
      (node (ref "U4") (pin "7") (pinfunction "PH_7") (pintype "passive"))
      (node (ref "U4") (pin "8") (pinfunction "PH_8") (pintype "passive"))
      (node (ref "U4") (pin "9") (pinfunction "PH_9") (pintype "passive"))
    )
    (net (code "10") (name "Net-(C191-Pad1)") (class "Default")
      (node (ref "C191") (pin "1") (pinfunction "1_1") (pintype "passive"))
      (node (ref "R58") (pin "2") (pinfunction "2_2") (pintype "passive"))
    )
    (net (code "11") (name "Net-(U2-EN)") (class "Default")
      (node (ref "R45") (pin "1") (pinfunction "1_1") (pintype "passive"))
      (node (ref "R47") (pin "2") (pinfunction "2_2") (pintype "passive"))
      (node (ref "U2") (pin "3") (pinfunction "EN_3") (pintype "input"))
    )
    (net (code "12") (name "Net-(U2-FB)") (class "Default")
      (node (ref "C166") (pin "2") (pinfunction "2_2") (pintype "passive"))
      (node (ref "R46") (pin "1") (pinfunction "1_1") (pintype "passive"))
      (node (ref "R48") (pin "2") (pinfunction "2_2") (pintype "passive"))
      (node (ref "U2") (pin "6") (pinfunction "FB_6") (pintype "input"))
    )
    (net (code "13") (name "Net-(U2-RON)") (class "Default")
      (node (ref "R49") (pin "1") (pinfunction "1_1") (pintype "passive"))
      (node (ref "U2") (pin "2") (pinfunction "RON_2") (pintype "passive"))
    )
    (net (code "14") (name "Net-(U2-SS)") (class "Default")
      (node (ref "C171") (pin "1") (pinfunction "1_1") (pintype "passive"))
      (node (ref "U2") (pin "5") (pinfunction "SS_5") (pintype "passive"))
    )
    (net (code "15") (name "Net-(U3-G)") (class "Default")
      (node (ref "R50") (pin "2") (pinfunction "2_2") (pintype "passive"))
      (node (ref "U3") (pin "4") (pinfunction "G_4") (pintype "passive"))
    )
    (net (code "16") (name "Net-(U4-BOOT)") (class "Default")
      (node (ref "C190") (pin "2") (pinfunction "2_2") (pintype "passive"))
      (node (ref "U4") (pin "5") (pinfunction "BOOT_5") (pintype "passive"))
    )
    (net (code "17") (name "Net-(U4-COMP)") (class "Default")
      (node (ref "C191") (pin "2") (pinfunction "2_2") (pintype "passive"))
      (node (ref "C195") (pin "2") (pinfunction "2_2") (pintype "passive"))
      (node (ref "U4") (pin "3") (pinfunction "COMP_3") (pintype "passive"))
    )
    (net (code "18") (name "Net-(U4-SS{slash}ENA)") (class "Default")
      (node (ref "C193") (pin "1") (pinfunction "1_1") (pintype "passive"))
      (node (ref "U4") (pin "26") (pinfunction "SS/ENA_26") (pintype "passive"))
    )
    (net (code "19") (name "Net-(U4-VBIAS)") (class "Default")
      (node (ref "C194") (pin "1") (pinfunction "1_1") (pintype "passive"))
      (node (ref "U4") (pin "25") (pinfunction "VBIAS_25") (pintype "passive"))
    )
    (net (code "20") (name "Net-(U4-VSENSE)") (class "Default")
      (node (ref "C195") (pin "1") (pinfunction "1_1") (pintype "passive"))
      (node (ref "R53") (pin "1") (pinfunction "1_1") (pintype "passive"))
      (node (ref "R55") (pin "1") (pinfunction "1_1") (pintype "passive"))
      (node (ref "R58") (pin "1") (pinfunction "1_1") (pintype "passive"))
      (node (ref "R59") (pin "2") (pinfunction "2_2") (pintype "passive"))
      (node (ref "U4") (pin "2") (pinfunction "VSENSE_2") (pintype "passive"))
    )
    (net (code "21") (name "Net-(U5-CS)") (class "Default")
      (node (ref "R57") (pin "2") (pinfunction "2_2") (pintype "passive"))
      (node (ref "U5") (pin "15") (pinfunction "CS_15") (pintype "input"))
    )
    (net (code "22") (name "Net-(U5-DRVH)") (class "Default")
      (node (ref "R50") (pin "1") (pinfunction "1_1") (pintype "passive"))
      (node (ref "U5") (pin "19") (pinfunction "DRVH_19") (pintype "output"))
    )
    (net (code "23") (name "Net-(U5-DRVL)") (class "Default")
      (node (ref "R54") (pin "1") (pinfunction "1_1") (pintype "passive"))
      (node (ref "U5") (pin "17") (pinfunction "DRVL_17") (pintype "output"))
    )
    (net (code "24") (name "Net-(U5-VBST)") (class "Default")
      (node (ref "C178") (pin "2") (pinfunction "2_2") (pintype "passive"))
      (node (ref "U5") (pin "20") (pinfunction "VBST_20") (pintype "power_in"))
    )
    (net (code "25") (name "Net-(U5-VDDQSET)") (class "Default")
      (node (ref "R51") (pin "1") (pinfunction "1_1") (pintype "passive"))
      (node (ref "R56") (pin "2") (pinfunction "2_2") (pintype "passive"))
      (node (ref "U5") (pin "10") (pinfunction "VDDQSET_10") (pintype "input"))
    )
    (net (code "26") (name "Net-(U6-G)") (class "Default")
      (node (ref "R54") (pin "2") (pinfunction "2_2") (pintype "passive"))
      (node (ref "U6") (pin "4") (pinfunction "G_4") (pintype "passive"))
    )
    (net (code "27") (name "Net-(U7-RESET_B)") (class "Default")
      (node (ref "R60") (pin "1") (pinfunction "1_1") (pintype "passive"))
      (node (ref "U7") (pin "16") (pinfunction "RESET_B_16") (pintype "passive"))
    )
    (net (code "28") (name "Net-(U9-RESET_B)") (class "Default")
      (node (ref "R61") (pin "1") (pinfunction "1_1") (pintype "passive"))
      (node (ref "U9") (pin "16") (pinfunction "RESET_B_16") (pintype "passive"))
    )
    (net (code "29") (name "VCC1V0") (class "Default")
      (node (ref "C179") (pin "2") (pinfunction "2_2") (pintype "passive"))
      (node (ref "C186") (pin "1") (pinfunction "1_1") (pintype "passive"))
      (node (ref "C187") (pin "1") (pinfunction "1_1") (pintype "passive"))
      (node (ref "L1") (pin "2") (pinfunction "2_2") (pintype "passive"))
      (node (ref "R53") (pin "2") (pinfunction "2_2") (pintype "passive"))
    )
    (net (code "30") (name "VCC1V5") (class "Default")
      (node (ref "C188") (pin "1") (pinfunction "1_1") (pintype "passive"))
      (node (ref "C189") (pin "1") (pinfunction "1_1") (pintype "passive"))
      (node (ref "L2") (pin "2") (pinfunction "2_2") (pintype "passive"))
      (node (ref "R51") (pin "2") (pinfunction "2_2") (pintype "passive"))
      (node (ref "U5") (pin "1") (pinfunction "VLDOIN_1") (pintype "power_in"))
      (node (ref "U5") (pin "9") (pinfunction "VDDQSNS_9") (pintype "passive"))
    )
    (net (code "31") (name "VCC1V8") (class "Default")
      (node (ref "C209") (pin "1") (pinfunction "1_1") (pintype "passive"))
      (node (ref "U9") (pin "13") (pinfunction "OUT_13") (pintype "passive"))
      (node (ref "U9") (pin "14") (pinfunction "OUT_14") (pintype "passive"))
    )
    (net (code "32") (name "VCC2V5") (class "Default")
      (node (ref "C208") (pin "1") (pinfunction "1_1") (pintype "passive"))
      (node (ref "U7") (pin "13") (pinfunction "OUT_13") (pintype "passive"))
      (node (ref "U7") (pin "14") (pinfunction "OUT_14") (pintype "passive"))
    )
    (net (code "33") (name "VCC3V3") (class "Default")
      (node (ref "C204") (pin "2") (pinfunction "2_2") (pintype "passive"))
      (node (ref "C205") (pin "2") (pinfunction "2_2") (pintype "passive"))
      (node (ref "U8") (pin "3") (pinfunction "OUT_3") (pintype "power_in"))
    )
    (net (code "34") (name "VCC3V3-A") (class "Default")
      (node (ref "C206") (pin "1") (pinfunction "1_1") (pintype "passive"))
      (node (ref "R61") (pin "2") (pinfunction "2_2") (pintype "passive"))
      (node (ref "U9") (pin "6") (pinfunction "IN_6") (pintype "passive"))
      (node (ref "U9") (pin "7") (pinfunction "IN_7") (pintype "passive"))
    )
    (net (code "35") (name "VCC3V3-B") (class "Default")
      (node (ref "C207") (pin "1") (pinfunction "1_1") (pintype "passive"))
      (node (ref "R60") (pin "2") (pinfunction "2_2") (pintype "passive"))
      (node (ref "U7") (pin "6") (pinfunction "IN_6") (pintype "passive"))
      (node (ref "U7") (pin "7") (pinfunction "IN_7") (pintype "passive"))
    )
    (net (code "36") (name "VCC5V0") (class "Default")
      (node (ref "C166") (pin "1") (pinfunction "1_1") (pintype "passive"))
      (node (ref "C167") (pin "1") (pinfunction "1_1") (pintype "passive"))
      (node (ref "C168") (pin "1") (pinfunction "1_1") (pintype "passive"))
      (node (ref "C169") (pin "1") (pinfunction "1_1") (pintype "passive"))
      (node (ref "C170") (pin "1") (pinfunction "1_1") (pintype "passive"))
      (node (ref "C176") (pin "1") (pinfunction "1_1") (pintype "passive"))
      (node (ref "C177") (pin "1") (pinfunction "1_1") (pintype "passive"))
      (node (ref "C180") (pin "1") (pinfunction "1_1") (pintype "passive"))
      (node (ref "C181") (pin "1") (pinfunction "1_1") (pintype "passive"))
      (node (ref "C182") (pin "1") (pinfunction "1_1") (pintype "passive"))
      (node (ref "C183") (pin "1") (pinfunction "1_1") (pintype "passive"))
      (node (ref "C184") (pin "1") (pinfunction "1_1") (pintype "passive"))
      (node (ref "C185") (pin "1") (pinfunction "1_1") (pintype "passive"))
      (node (ref "C201") (pin "1") (pinfunction "1_1") (pintype "passive"))
      (node (ref "C202") (pin "2") (pinfunction "2_2") (pintype "passive"))
      (node (ref "C203") (pin "2") (pinfunction "2_2") (pintype "passive"))
      (node (ref "R46") (pin "2") (pinfunction "2_2") (pintype "passive"))
      (node (ref "R52") (pin "2") (pinfunction "2_2") (pintype "passive"))
      (node (ref "R57") (pin "1") (pinfunction "1_1") (pintype "passive"))
      (node (ref "U2") (pin "7") (pinfunction "VOUT_7") (pintype "output"))
      (node (ref "U3") (pin "5") (pinfunction "D_5") (pintype "passive"))
      (node (ref "U3") (pin "6") (pinfunction "D_6") (pintype "passive"))
      (node (ref "U3") (pin "7") (pinfunction "D_7") (pintype "passive"))
      (node (ref "U3") (pin "8") (pinfunction "D_8") (pintype "passive"))
      (node (ref "U4") (pin "20") (pinfunction "VIN_20") (pintype "passive"))
      (node (ref "U4") (pin "21") (pinfunction "VIN_21") (pintype "passive"))
      (node (ref "U4") (pin "22") (pinfunction "VIN_22") (pintype "passive"))
      (node (ref "U4") (pin "23") (pinfunction "VIN_23") (pintype "passive"))
      (node (ref "U4") (pin "24") (pinfunction "VIN_24") (pintype "passive"))
      (node (ref "U4") (pin "27") (pinfunction "FSEL_27") (pintype "passive"))
      (node (ref "U5") (pin "14") (pinfunction "V5IN_14") (pintype "power_in"))
      (node (ref "U5") (pin "8") (pinfunction "COMP_8") (pintype "passive"))
      (node (ref "U8") (pin "1") (pinfunction "IN_1") (pintype "power_in"))
    )
    (net (code "37") (name "VCC_IN") (class "Default")
      (node (ref "C162") (pin "1") (pinfunction "1_1") (pintype "passive"))
      (node (ref "C163") (pin "1") (pinfunction "1_1") (pintype "passive"))
      (node (ref "C164") (pin "1") (pinfunction "1_1") (pintype "passive"))
      (node (ref "C165") (pin "1") (pinfunction "1_1") (pintype "passive"))
      (node (ref "C172") (pin "1") (pinfunction "1_1") (pintype "passive"))
      (node (ref "C173") (pin "1") (pinfunction "1_1") (pintype "passive"))
      (node (ref "C174") (pin "1") (pinfunction "1_1") (pintype "passive"))
      (node (ref "R45") (pin "2") (pinfunction "2_2") (pintype "passive"))
      (node (ref "R49") (pin "2") (pinfunction "2_2") (pintype "passive"))
      (node (ref "SW1") (pin "2") (pinfunction "2_2") (pintype "passive"))
      (node (ref "U2") (pin "1") (pinfunction "VIN_1") (pintype "input"))
    )
    (net (code "38") (name "VCC_JACK") (class "Default")
      (node (ref "C175") (pin "1") (pinfunction "1_1") (pintype "passive"))
      (node (ref "J1") (pin "1") (pinfunction "1_1") (pintype "power_in"))
      (node (ref "SW1") (pin "1") (pinfunction "1_1") (pintype "passive"))
    )
    (net (code "39") (name "unconnected-(SW1-Pad3)") (class "Default")
      (node (ref "SW1") (pin "3") (pinfunction "3_3") (pintype "passive"))
    )
    (net (code "40") (name "unconnected-(U4-PH-Pad6)") (class "Default")
      (node (ref "U4") (pin "6") (pinfunction "PH_6") (pintype "passive"))
    )
    (net (code "41") (name "unconnected-(U4-RT-Pad28)") (class "Default")
      (node (ref "U4") (pin "28") (pinfunction "RT_28") (pintype "passive"))
    )
  )
)
